# SirenaNextionNRF52.net
KiCad netlist of a schematic drawn in EAGLE
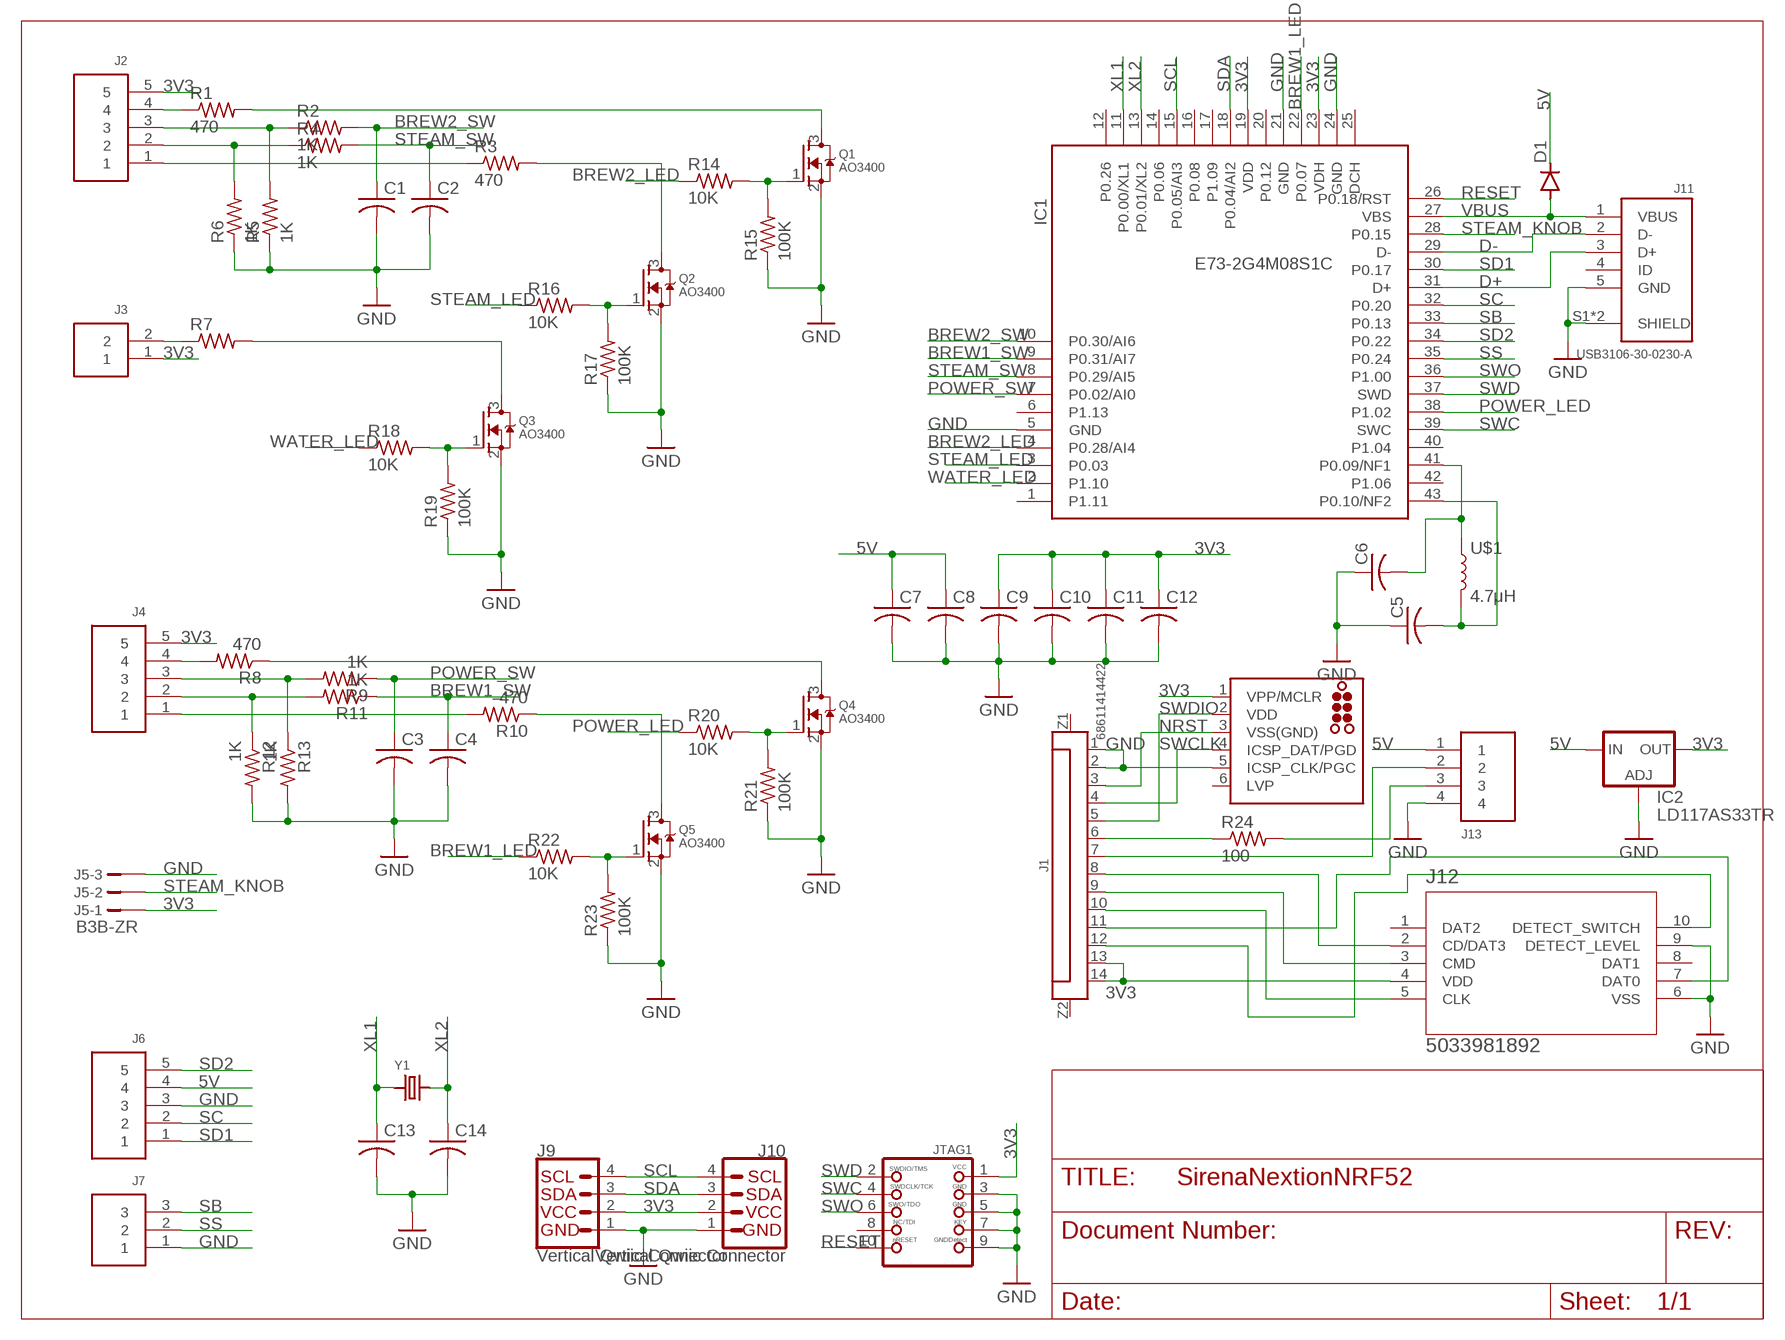
[diagram p0: schematic, sheet 1]

(export (version "E")
  (design (tool "Eeschema 10.0.6"))
  (components
    (comp (ref "C1")
      (value "C-USC0603")
      (footprint "eagle-import:C0603")
      (libsource (lib "eagle-import") (part "C-USC0603"))
    )
    (comp (ref "C2")
      (value "C-USC0603")
      (footprint "eagle-import:C0603")
      (libsource (lib "eagle-import") (part "C-USC0603"))
    )
    (comp (ref "C3")
      (value "C-USC0603")
      (footprint "eagle-import:C0603")
      (libsource (lib "eagle-import") (part "C-USC0603"))
    )
    (comp (ref "C4")
      (value "C-USC0603")
      (footprint "eagle-import:C0603")
      (libsource (lib "eagle-import") (part "C-USC0603"))
    )
    (comp (ref "C5")
      (value "C-USC0603")
      (footprint "eagle-import:C0603")
      (libsource (lib "eagle-import") (part "C-USC0603"))
    )
    (comp (ref "C6")
      (value "C-USC0603")
      (footprint "eagle-import:C0603")
      (libsource (lib "eagle-import") (part "C-USC0603"))
    )
    (comp (ref "C7")
      (value "C-USC0603")
      (footprint "eagle-import:C0603")
      (libsource (lib "eagle-import") (part "C-USC0603"))
    )
    (comp (ref "C8")
      (value "C-USC0603")
      (footprint "eagle-import:C0603")
      (libsource (lib "eagle-import") (part "C-USC0603"))
    )
    (comp (ref "C9")
      (value "C-USC0603")
      (footprint "eagle-import:C0603")
      (libsource (lib "eagle-import") (part "C-USC0603"))
    )
    (comp (ref "C10")
      (value "C-USC0603")
      (footprint "eagle-import:C0603")
      (libsource (lib "eagle-import") (part "C-USC0603"))
    )
    (comp (ref "C11")
      (value "C-USC0603")
      (footprint "eagle-import:C0603")
      (libsource (lib "eagle-import") (part "C-USC0603"))
    )
    (comp (ref "C12")
      (value "C-USC0603")
      (footprint "eagle-import:C0603")
      (libsource (lib "eagle-import") (part "C-USC0603"))
    )
    (comp (ref "C13")
      (value "C-USC0603")
      (footprint "eagle-import:C0603")
      (libsource (lib "eagle-import") (part "C-USC0603"))
    )
    (comp (ref "C14")
      (value "C-USC0603")
      (footprint "eagle-import:C0603")
      (libsource (lib "eagle-import") (part "C-USC0603"))
    )
    (comp (ref "D1")
      (value "DIODE-SOD323-R")
      (footprint "eagle-import:SOD323-R")
      (libsource (lib "eagle-import") (part "DIODE-SOD323-R"))
    )
    (comp (ref "IC1")
      (value "E73-2G4M08S1C")
      (footprint "eagle-import:SMD")
      (libsource (lib "eagle-import") (part "E73-2G4M08S1C"))
    )
    (comp (ref "IC2")
      (value "LD117AS33TR")
      (footprint "eagle-import:SOT223")
      (libsource (lib "eagle-import") (part "LD117A?S33TR"))
    )
    (comp (ref "J1")
      (value "68611414422")
      (footprint "eagle-import:68611414422")
      (libsource (lib "eagle-import") (part "6861XX14422_68611414422"))
    )
    (comp (ref "J2")
      (value "5PINB5B-PH-SM4-TB")
      (footprint "eagle-import:B5B-PH-SM4-TB")
      (libsource (lib "eagle-import") (part "5PINB5B-PH-SM4-TB"))
    )
    (comp (ref "J3")
      (value "2PINB2B-PH-SM4-TB")
      (footprint "eagle-import:B2B-PH-SM4-TB")
      (libsource (lib "eagle-import") (part "2PINB2B-PH-SM4-TB"))
    )
    (comp (ref "J4")
      (value "5PINB5B-PH-SM4-TB")
      (footprint "eagle-import:B5B-PH-SM4-TB")
      (libsource (lib "eagle-import") (part "5PINB5B-PH-SM4-TB"))
    )
    (comp (ref "J5")
      (value "B3B-ZR")
      (footprint "eagle-import:B3B-ZR")
      (libsource (lib "eagle-import") (part "?3B-ZRB"))
    )
    (comp (ref "J6")
      (value "5PINB5B-PH-SM4-TB")
      (footprint "eagle-import:B5B-PH-SM4-TB")
      (libsource (lib "eagle-import") (part "5PINB5B-PH-SM4-TB"))
    )
    (comp (ref "J7")
      (value "3PINB3B-PH-SM4-TB")
      (footprint "eagle-import:B3B-PH-SM4-TB")
      (libsource (lib "eagle-import") (part "3PINB3B-PH-SM4-TB"))
    )
    (comp (ref "J9")
      (value "Vertical Qwiic Connector")
      (footprint "eagle-import:JST04_1MM_VERT")
      (libsource (lib "eagle-import") (part "QWIIC_CONNECTOR"))
    )
    (comp (ref "J10")
      (value "Vertical Qwiic Connector")
      (footprint "eagle-import:JST04_1MM_VERT")
      (libsource (lib "eagle-import") (part "QWIIC_CONNECTOR"))
    )
    (comp (ref "J11")
      (value "USB3106-30-0230-A")
      (footprint "eagle-import:USB3106-30-0230-A")
      (fields
        (field (name "DIGIKEY_PARTNO") "2073-USB3106-30-0230-ATR-ND")
        (field (name "MANUFACTURER") "GCT")
        (field (name "CREATED_BY") "PCBLayout.com")
      )
      (libsource (lib "eagle-import") (part "USB3106-30-0230-A"))
    )
    (comp (ref "J12")
      (value "5033981892")
      (footprint "eagle-import:503398-1892_MOL")
      (fields (field (name "COPYRIGHT") "Copyright (C) 2022 Ultra Librarian. All rights reserved."))
      (libsource (lib "eagle-import") (part "5033981892"))
    )
    (comp (ref "J13")
      (value "4PIN")
      (footprint "eagle-import:B4B-XH-K-S")
      (libsource (lib "eagle-import") (part "4PIN"))
    )
    (comp (ref "J14")
      (value "TC2030-MCP-NL")
      (footprint "eagle-import:TC2030-MCP-NL")
      (libsource (lib "eagle-import") (part "TC2030-MCP-NL"))
    )
    (comp (ref "JTAG1")
      (value "JTAG-CORTEXM3")
      (footprint "eagle-import:2X05_1.27MM_SMT")
      (libsource (lib "eagle-import") (part "JTAG-CORTEXM3"))
    )
    (comp (ref "Q1")
      (value "AO3400")
      (footprint "eagle-import:SOT23")
      (libsource (lib "eagle-import") (part "MOSFET-NREFLOW"))
    )
    (comp (ref "Q2")
      (value "AO3400")
      (footprint "eagle-import:SOT23")
      (libsource (lib "eagle-import") (part "MOSFET-NREFLOW"))
    )
    (comp (ref "Q3")
      (value "AO3400")
      (footprint "eagle-import:SOT23")
      (libsource (lib "eagle-import") (part "MOSFET-NREFLOW"))
    )
    (comp (ref "Q4")
      (value "AO3400")
      (footprint "eagle-import:SOT23")
      (libsource (lib "eagle-import") (part "MOSFET-NREFLOW"))
    )
    (comp (ref "Q5")
      (value "AO3400")
      (footprint "eagle-import:SOT23")
      (libsource (lib "eagle-import") (part "MOSFET-NREFLOW"))
    )
    (comp (ref "R1")
      (value "470")
      (footprint "eagle-import:R0603")
      (libsource (lib "eagle-import") (part "R-US_R0603"))
    )
    (comp (ref "R2")
      (value "1K")
      (footprint "eagle-import:R0603")
      (libsource (lib "eagle-import") (part "R-US_R0603"))
    )
    (comp (ref "R3")
      (value "470")
      (footprint "eagle-import:R0603")
      (libsource (lib "eagle-import") (part "R-US_R0603"))
    )
    (comp (ref "R4")
      (value "1K")
      (footprint "eagle-import:R0603")
      (libsource (lib "eagle-import") (part "R-US_R0603"))
    )
    (comp (ref "R5")
      (value "1K")
      (footprint "eagle-import:R0603")
      (libsource (lib "eagle-import") (part "R-US_R0603"))
    )
    (comp (ref "R6")
      (value "1K")
      (footprint "eagle-import:R0603")
      (libsource (lib "eagle-import") (part "R-US_R0603"))
    )
    (comp (ref "R7")
      (value "R-US_R0603")
      (footprint "eagle-import:R0603")
      (libsource (lib "eagle-import") (part "R-US_R0603"))
    )
    (comp (ref "R8")
      (value "470")
      (footprint "eagle-import:R0603")
      (libsource (lib "eagle-import") (part "R-US_R0603"))
    )
    (comp (ref "R9")
      (value "1K")
      (footprint "eagle-import:R0603")
      (libsource (lib "eagle-import") (part "R-US_R0603"))
    )
    (comp (ref "R10")
      (value "470")
      (footprint "eagle-import:R0603")
      (libsource (lib "eagle-import") (part "R-US_R0603"))
    )
    (comp (ref "R11")
      (value "1K")
      (footprint "eagle-import:R0603")
      (libsource (lib "eagle-import") (part "R-US_R0603"))
    )
    (comp (ref "R12")
      (value "1K")
      (footprint "eagle-import:R0603")
      (libsource (lib "eagle-import") (part "R-US_R0603"))
    )
    (comp (ref "R13")
      (value "1K")
      (footprint "eagle-import:R0603")
      (libsource (lib "eagle-import") (part "R-US_R0603"))
    )
    (comp (ref "R14")
      (value "10K")
      (footprint "eagle-import:R0603")
      (libsource (lib "eagle-import") (part "R-US_R0603"))
    )
    (comp (ref "R15")
      (value "100K")
      (footprint "eagle-import:R0603")
      (libsource (lib "eagle-import") (part "R-US_R0603"))
    )
    (comp (ref "R16")
      (value "10K")
      (footprint "eagle-import:R0603")
      (libsource (lib "eagle-import") (part "R-US_R0603"))
    )
    (comp (ref "R17")
      (value "100K")
      (footprint "eagle-import:R0603")
      (libsource (lib "eagle-import") (part "R-US_R0603"))
    )
    (comp (ref "R18")
      (value "10K")
      (footprint "eagle-import:R0603")
      (libsource (lib "eagle-import") (part "R-US_R0603"))
    )
    (comp (ref "R19")
      (value "100K")
      (footprint "eagle-import:R0603")
      (libsource (lib "eagle-import") (part "R-US_R0603"))
    )
    (comp (ref "R20")
      (value "10K")
      (footprint "eagle-import:R0603")
      (libsource (lib "eagle-import") (part "R-US_R0603"))
    )
    (comp (ref "R21")
      (value "100K")
      (footprint "eagle-import:R0603")
      (libsource (lib "eagle-import") (part "R-US_R0603"))
    )
    (comp (ref "R22")
      (value "10K")
      (footprint "eagle-import:R0603")
      (libsource (lib "eagle-import") (part "R-US_R0603"))
    )
    (comp (ref "R23")
      (value "100K")
      (footprint "eagle-import:R0603")
      (libsource (lib "eagle-import") (part "R-US_R0603"))
    )
    (comp (ref "R24")
      (value "100")
      (footprint "eagle-import:R0603")
      (libsource (lib "eagle-import") (part "R-US_R0603"))
    )
    (comp (ref "U$1")
      (value "4.7μH")
      (footprint "eagle-import:W3102")
      (libsource (lib "eagle-import") (part "RFID_ANTENNA_W3102"))
    )
    (comp (ref "Y1")
      (value "CRYSTAL8X3.8SMT")
      (footprint "eagle-import:CRYSTAL_8X3.8")
      (libsource (lib "eagle-import") (part "CRYSTAL8X3.8SMT"))
    )
  )
  (nets
    (net (code "1") (name "/3V3") (class "Default")
      (node (ref "C10") (pin "1") (pinfunction "1_1") (pintype "passive"))
      (node (ref "C11") (pin "1") (pinfunction "1_1") (pintype "passive"))
      (node (ref "C12") (pin "1") (pinfunction "1_1") (pintype "passive"))
      (node (ref "C9") (pin "1") (pinfunction "1_1") (pintype "passive"))
      (node (ref "IC1") (pin "19") (pinfunction "VDD_19") (pintype "power_in"))
      (node (ref "IC1") (pin "23") (pinfunction "VDH_23") (pintype "power_in"))
      (node (ref "IC2") (pin "4") (pinfunction "OUT_4") (pintype "passive"))
      (node (ref "J1") (pin "13") (pinfunction "13_13") (pintype "passive"))
      (node (ref "J1") (pin "14") (pinfunction "14_14") (pintype "passive"))
      (node (ref "J10") (pin "2") (pinfunction "2_2") (pintype "power_in"))
      (node (ref "J12") (pin "4") (pinfunction "VDD_4") (pintype "power_in"))
      (node (ref "J14") (pin "1") (pinfunction "VPP/MCLR_1") (pintype "passive"))
      (node (ref "J2") (pin "5") (pinfunction "5_5") (pintype "bidirectional"))
      (node (ref "J3") (pin "1") (pinfunction "1_1") (pintype "bidirectional"))
      (node (ref "J4") (pin "5") (pinfunction "5_5") (pintype "bidirectional"))
      (node (ref "J5") (pin "1") (pinfunction "1_1") (pintype "passive"))
      (node (ref "J9") (pin "2") (pinfunction "2_2") (pintype "power_in"))
      (node (ref "JTAG1") (pin "1") (pinfunction "1_1") (pintype "passive"))
    )
    (net (code "2") (name "/5V") (class "Default")
      (node (ref "C7") (pin "1") (pinfunction "1_1") (pintype "passive"))
      (node (ref "C8") (pin "1") (pinfunction "1_1") (pintype "passive"))
      (node (ref "D1") (pin "C") (pinfunction "C_C") (pintype "passive"))
      (node (ref "IC2") (pin "3") (pinfunction "IN_3") (pintype "input"))
      (node (ref "J13") (pin "1") (pinfunction "1_1") (pintype "bidirectional"))
      (node (ref "J6") (pin "4") (pinfunction "4_4") (pintype "bidirectional"))
    )
    (net (code "3") (name "/BREW1_LED") (class "Default")
      (node (ref "IC1") (pin "22") (pinfunction "P0.07_22") (pintype "bidirectional"))
      (node (ref "R22") (pin "1") (pinfunction "1_1") (pintype "passive"))
    )
    (net (code "4") (name "/BREW1_SW") (class "Default")
      (node (ref "C4") (pin "1") (pinfunction "1_1") (pintype "passive"))
      (node (ref "IC1") (pin "9") (pinfunction "P0.31/AI7_9") (pintype "bidirectional"))
      (node (ref "R11") (pin "1") (pinfunction "1_1") (pintype "passive"))
    )
    (net (code "5") (name "/BREW2_LED") (class "Default")
      (node (ref "IC1") (pin "4") (pinfunction "P0.28/AI4_4") (pintype "bidirectional"))
      (node (ref "R14") (pin "1") (pinfunction "1_1") (pintype "passive"))
    )
    (net (code "6") (name "/BREW2_SW") (class "Default")
      (node (ref "C1") (pin "1") (pinfunction "1_1") (pintype "passive"))
      (node (ref "IC1") (pin "10") (pinfunction "P0.30/AI6_10") (pintype "bidirectional"))
      (node (ref "R2") (pin "2") (pinfunction "2_2") (pintype "passive"))
    )
    (net (code "7") (name "/D+") (class "Default")
      (node (ref "IC1") (pin "31") (pinfunction "D+_31") (pintype "bidirectional"))
      (node (ref "J11") (pin "3") (pinfunction "D+_3") (pintype "passive"))
    )
    (net (code "8") (name "/D-") (class "Default")
      (node (ref "IC1") (pin "29") (pinfunction "D-_29") (pintype "bidirectional"))
      (node (ref "J11") (pin "2") (pinfunction "D-_2") (pintype "passive"))
    )
    (net (code "9") (name "/NRST") (class "Default")
      (node (ref "J1") (pin "3") (pinfunction "3_3") (pintype "passive"))
      (node (ref "J14") (pin "3") (pinfunction "VSS(GND)_3") (pintype "power_in"))
    )
    (net (code "10") (name "/POWER_LED") (class "Default")
      (node (ref "IC1") (pin "38") (pinfunction "P1.02_38") (pintype "bidirectional"))
      (node (ref "R20") (pin "1") (pinfunction "1_1") (pintype "passive"))
    )
    (net (code "11") (name "/POWER_SW") (class "Default")
      (node (ref "C3") (pin "1") (pinfunction "1_1") (pintype "passive"))
      (node (ref "IC1") (pin "7") (pinfunction "P0.02/AI0_7") (pintype "bidirectional"))
      (node (ref "R9") (pin "1") (pinfunction "1_1") (pintype "passive"))
    )
    (net (code "12") (name "/RESET") (class "Default")
      (node (ref "IC1") (pin "26") (pinfunction "P0.18/RST_26") (pintype "bidirectional"))
      (node (ref "JTAG1") (pin "10") (pinfunction "10_10") (pintype "passive"))
    )
    (net (code "13") (name "/SB") (class "Default")
      (node (ref "IC1") (pin "33") (pinfunction "P0.13_33") (pintype "bidirectional"))
      (node (ref "J7") (pin "3") (pinfunction "3_3") (pintype "bidirectional"))
    )
    (net (code "14") (name "/SC") (class "Default")
      (node (ref "IC1") (pin "32") (pinfunction "P0.20_32") (pintype "bidirectional"))
      (node (ref "J6") (pin "2") (pinfunction "2_2") (pintype "bidirectional"))
    )
    (net (code "15") (name "/SCL") (class "Default")
      (node (ref "IC1") (pin "15") (pinfunction "P0.05/AI3_15") (pintype "bidirectional"))
      (node (ref "J10") (pin "4") (pinfunction "4_4") (pintype "passive"))
      (node (ref "J9") (pin "4") (pinfunction "4_4") (pintype "passive"))
    )
    (net (code "16") (name "/SD1") (class "Default")
      (node (ref "IC1") (pin "30") (pinfunction "P0.17_30") (pintype "bidirectional"))
      (node (ref "J6") (pin "1") (pinfunction "1_1") (pintype "bidirectional"))
    )
    (net (code "17") (name "/SD2") (class "Default")
      (node (ref "IC1") (pin "34") (pinfunction "P0.22_34") (pintype "bidirectional"))
      (node (ref "J6") (pin "5") (pinfunction "5_5") (pintype "bidirectional"))
    )
    (net (code "18") (name "/SDA") (class "Default")
      (node (ref "IC1") (pin "18") (pinfunction "P0.04/AI2_18") (pintype "bidirectional"))
      (node (ref "J10") (pin "3") (pinfunction "3_3") (pintype "passive"))
      (node (ref "J9") (pin "3") (pinfunction "3_3") (pintype "passive"))
    )
    (net (code "19") (name "/SS") (class "Default")
      (node (ref "IC1") (pin "35") (pinfunction "P0.24_35") (pintype "bidirectional"))
      (node (ref "J7") (pin "2") (pinfunction "2_2") (pintype "bidirectional"))
    )
    (net (code "20") (name "/STEAM_KNOB") (class "Default")
      (node (ref "IC1") (pin "28") (pinfunction "P0.15_28") (pintype "bidirectional"))
      (node (ref "J5") (pin "2") (pinfunction "1_2") (pintype "passive"))
    )
    (net (code "21") (name "/STEAM_LED") (class "Default")
      (node (ref "IC1") (pin "3") (pinfunction "P0.03_3") (pintype "bidirectional"))
      (node (ref "R16") (pin "1") (pinfunction "1_1") (pintype "passive"))
    )
    (net (code "22") (name "/STEAM_SW") (class "Default")
      (node (ref "C2") (pin "1") (pinfunction "1_1") (pintype "passive"))
      (node (ref "IC1") (pin "8") (pinfunction "P0.29/AI5_8") (pintype "bidirectional"))
      (node (ref "R4") (pin "2") (pinfunction "2_2") (pintype "passive"))
    )
    (net (code "23") (name "/SWC") (class "Default")
      (node (ref "IC1") (pin "39") (pinfunction "SWC_39") (pintype "bidirectional"))
      (node (ref "JTAG1") (pin "4") (pinfunction "4_4") (pintype "passive"))
    )
    (net (code "24") (name "/SWCLK") (class "Default")
      (node (ref "J1") (pin "4") (pinfunction "4_4") (pintype "passive"))
      (node (ref "J14") (pin "4") (pinfunction "ICSP_DAT/PGD_4") (pintype "bidirectional"))
    )
    (net (code "25") (name "/SWD") (class "Default")
      (node (ref "IC1") (pin "37") (pinfunction "SWD_37") (pintype "bidirectional"))
      (node (ref "JTAG1") (pin "2") (pinfunction "2_2") (pintype "passive"))
    )
    (net (code "26") (name "/SWDIO") (class "Default")
      (node (ref "J1") (pin "5") (pinfunction "5_5") (pintype "passive"))
      (node (ref "J14") (pin "2") (pinfunction "VDD_2") (pintype "power_in"))
    )
    (net (code "27") (name "/SWO") (class "Default")
      (node (ref "IC1") (pin "36") (pinfunction "P1.00_36") (pintype "bidirectional"))
      (node (ref "JTAG1") (pin "6") (pinfunction "6_6") (pintype "passive"))
    )
    (net (code "28") (name "/VBUS") (class "Default")
      (node (ref "D1") (pin "A") (pinfunction "A_A") (pintype "passive"))
      (node (ref "IC1") (pin "27") (pinfunction "VBS_27") (pintype "power_in"))
      (node (ref "J11") (pin "1") (pinfunction "VBUS_1") (pintype "passive"))
    )
    (net (code "29") (name "/WATER_LED") (class "Default")
      (node (ref "IC1") (pin "2") (pinfunction "P1.10_2") (pintype "bidirectional"))
      (node (ref "R18") (pin "1") (pinfunction "1_1") (pintype "passive"))
    )
    (net (code "30") (name "/XL1") (class "Default")
      (node (ref "C13") (pin "1") (pinfunction "1_1") (pintype "passive"))
      (node (ref "IC1") (pin "11") (pinfunction "P0.00/XL1_11") (pintype "bidirectional"))
      (node (ref "Y1") (pin "P$1") (pinfunction "1_P$1") (pintype "passive"))
    )
    (net (code "31") (name "/XL2") (class "Default")
      (node (ref "C14") (pin "1") (pinfunction "1_1") (pintype "passive"))
      (node (ref "IC1") (pin "13") (pinfunction "P0.01/XL2_13") (pintype "bidirectional"))
      (node (ref "Y1") (pin "P$4") (pinfunction "2_P$4") (pintype "passive"))
    )
    (net (code "32") (name "GND") (class "Default")
      (node (ref "C1") (pin "2") (pinfunction "2_2") (pintype "passive"))
      (node (ref "C10") (pin "2") (pinfunction "2_2") (pintype "passive"))
      (node (ref "C11") (pin "2") (pinfunction "2_2") (pintype "passive"))
      (node (ref "C12") (pin "2") (pinfunction "2_2") (pintype "passive"))
      (node (ref "C13") (pin "2") (pinfunction "2_2") (pintype "passive"))
      (node (ref "C14") (pin "2") (pinfunction "2_2") (pintype "passive"))
      (node (ref "C2") (pin "2") (pinfunction "2_2") (pintype "passive"))
      (node (ref "C3") (pin "2") (pinfunction "2_2") (pintype "passive"))
      (node (ref "C4") (pin "2") (pinfunction "2_2") (pintype "passive"))
      (node (ref "C5") (pin "1") (pinfunction "1_1") (pintype "passive"))
      (node (ref "C6") (pin "1") (pinfunction "1_1") (pintype "passive"))
      (node (ref "C7") (pin "2") (pinfunction "2_2") (pintype "passive"))
      (node (ref "C8") (pin "2") (pinfunction "2_2") (pintype "passive"))
      (node (ref "C9") (pin "2") (pinfunction "2_2") (pintype "passive"))
      (node (ref "IC1") (pin "21") (pinfunction "GND_21") (pintype "power_in"))
      (node (ref "IC1") (pin "24") (pinfunction "GND_24") (pintype "power_in"))
      (node (ref "IC1") (pin "5") (pinfunction "GND_5") (pintype "power_in"))
      (node (ref "IC2") (pin "1") (pinfunction "ADJ_1") (pintype "input"))
      (node (ref "J1") (pin "1") (pinfunction "1_1") (pintype "passive"))
      (node (ref "J1") (pin "2") (pinfunction "2_2") (pintype "passive"))
      (node (ref "J10") (pin "1") (pinfunction "1_1") (pintype "power_in"))
      (node (ref "J11") (pin "5") (pinfunction "GND_5") (pintype "passive"))
      (node (ref "J11") (pin "S1") (pinfunction "SHIELD_S1") (pintype "power_in"))
      (node (ref "J11") (pin "S2") (pinfunction "SHIELD_S2") (pintype "power_in"))
      (node (ref "J12") (pin "6") (pinfunction "VSS_6") (pintype "passive"))
      (node (ref "J12") (pin "9") (pinfunction "DETECT_LEVEL_9") (pintype "passive"))
      (node (ref "J13") (pin "4") (pinfunction "4_4") (pintype "bidirectional"))
      (node (ref "J14") (pin "5") (pinfunction "ICSP_CLK/PGC_5") (pintype "output"))
      (node (ref "J5") (pin "3") (pinfunction "1_3") (pintype "passive"))
      (node (ref "J6") (pin "3") (pinfunction "3_3") (pintype "bidirectional"))
      (node (ref "J7") (pin "1") (pinfunction "1_1") (pintype "bidirectional"))
      (node (ref "J9") (pin "1") (pinfunction "1_1") (pintype "power_in"))
      (node (ref "JTAG1") (pin "3") (pinfunction "3_3") (pintype "passive"))
      (node (ref "JTAG1") (pin "5") (pinfunction "5_5") (pintype "passive"))
      (node (ref "JTAG1") (pin "7") (pinfunction "7_7") (pintype "passive"))
      (node (ref "JTAG1") (pin "9") (pinfunction "9_9") (pintype "passive"))
      (node (ref "Q1") (pin "2") (pinfunction "S_2") (pintype "bidirectional"))
      (node (ref "Q2") (pin "2") (pinfunction "S_2") (pintype "bidirectional"))
      (node (ref "Q3") (pin "2") (pinfunction "S_2") (pintype "bidirectional"))
      (node (ref "Q4") (pin "2") (pinfunction "S_2") (pintype "bidirectional"))
      (node (ref "Q5") (pin "2") (pinfunction "S_2") (pintype "bidirectional"))
      (node (ref "R12") (pin "2") (pinfunction "2_2") (pintype "passive"))
      (node (ref "R13") (pin "2") (pinfunction "2_2") (pintype "passive"))
      (node (ref "R15") (pin "1") (pinfunction "1_1") (pintype "passive"))
      (node (ref "R17") (pin "1") (pinfunction "1_1") (pintype "passive"))
      (node (ref "R19") (pin "1") (pinfunction "1_1") (pintype "passive"))
      (node (ref "R21") (pin "1") (pinfunction "1_1") (pintype "passive"))
      (node (ref "R23") (pin "1") (pinfunction "1_1") (pintype "passive"))
      (node (ref "R5") (pin "1") (pinfunction "1_1") (pintype "passive"))
      (node (ref "R6") (pin "1") (pinfunction "1_1") (pintype "passive"))
    )
    (net (code "33") (name "Net-(IC1-P0.09{slash}NF1)") (class "Default")
      (node (ref "C6") (pin "2") (pinfunction "2_2") (pintype "passive"))
      (node (ref "IC1") (pin "41") (pinfunction "P0.09/NF1_41") (pintype "bidirectional"))
      (node (ref "U$1") (pin "1") (pinfunction "1_1") (pintype "passive"))
    )
    (net (code "34") (name "Net-(IC1-P0.10{slash}NF2)") (class "Default")
      (node (ref "C5") (pin "2") (pinfunction "2_2") (pintype "passive"))
      (node (ref "IC1") (pin "43") (pinfunction "P0.10/NF2_43") (pintype "bidirectional"))
      (node (ref "U$1") (pin "2") (pinfunction "2_2") (pintype "passive"))
    )
    (net (code "35") (name "Net-(J1-Pad6)") (class "Default")
      (node (ref "J1") (pin "6") (pinfunction "6_6") (pintype "passive"))
      (node (ref "R24") (pin "1") (pinfunction "1_1") (pintype "passive"))
    )
    (net (code "36") (name "Net-(J1-Pad7)") (class "Default")
      (node (ref "J1") (pin "7") (pinfunction "7_7") (pintype "passive"))
      (node (ref "J13") (pin "2") (pinfunction "2_2") (pintype "bidirectional"))
    )
    (net (code "37") (name "Net-(J2-Pad1)") (class "Default")
      (node (ref "J2") (pin "1") (pinfunction "1_1") (pintype "bidirectional"))
      (node (ref "R3") (pin "1") (pinfunction "1_1") (pintype "passive"))
    )
    (net (code "38") (name "Net-(J2-Pad2)") (class "Default")
      (node (ref "J2") (pin "2") (pinfunction "2_2") (pintype "bidirectional"))
      (node (ref "R4") (pin "1") (pinfunction "1_1") (pintype "passive"))
      (node (ref "R6") (pin "2") (pinfunction "2_2") (pintype "passive"))
    )
    (net (code "39") (name "Net-(J2-Pad3)") (class "Default")
      (node (ref "J2") (pin "3") (pinfunction "3_3") (pintype "bidirectional"))
      (node (ref "R2") (pin "1") (pinfunction "1_1") (pintype "passive"))
      (node (ref "R5") (pin "2") (pinfunction "2_2") (pintype "passive"))
    )
    (net (code "40") (name "Net-(J2-Pad4)") (class "Default")
      (node (ref "J2") (pin "4") (pinfunction "4_4") (pintype "bidirectional"))
      (node (ref "R1") (pin "1") (pinfunction "1_1") (pintype "passive"))
    )
    (net (code "41") (name "Net-(J3-Pad2)") (class "Default")
      (node (ref "J3") (pin "2") (pinfunction "2_2") (pintype "bidirectional"))
      (node (ref "R7") (pin "1") (pinfunction "1_1") (pintype "passive"))
    )
    (net (code "42") (name "Net-(J4-Pad1)") (class "Default")
      (node (ref "J4") (pin "1") (pinfunction "1_1") (pintype "bidirectional"))
      (node (ref "R10") (pin "2") (pinfunction "2_2") (pintype "passive"))
    )
    (net (code "43") (name "Net-(J4-Pad2)") (class "Default")
      (node (ref "J4") (pin "2") (pinfunction "2_2") (pintype "bidirectional"))
      (node (ref "R11") (pin "2") (pinfunction "2_2") (pintype "passive"))
      (node (ref "R12") (pin "1") (pinfunction "1_1") (pintype "passive"))
    )
    (net (code "44") (name "Net-(J4-Pad3)") (class "Default")
      (node (ref "J4") (pin "3") (pinfunction "3_3") (pintype "bidirectional"))
      (node (ref "R13") (pin "1") (pinfunction "1_1") (pintype "passive"))
      (node (ref "R9") (pin "2") (pinfunction "2_2") (pintype "passive"))
    )
    (net (code "45") (name "Net-(J4-Pad4)") (class "Default")
      (node (ref "J4") (pin "4") (pinfunction "4_4") (pintype "bidirectional"))
      (node (ref "R8") (pin "2") (pinfunction "2_2") (pintype "passive"))
    )
    (net (code "46") (name "Net-(J12-CD{slash}DAT3)") (class "Default")
      (node (ref "J1") (pin "8") (pinfunction "8_8") (pintype "passive"))
      (node (ref "J12") (pin "2") (pinfunction "CD/DAT3_2") (pintype "passive"))
    )
    (net (code "47") (name "Net-(J12-CLK)") (class "Default")
      (node (ref "J1") (pin "10") (pinfunction "10_10") (pintype "passive"))
      (node (ref "J12") (pin "5") (pinfunction "CLK_5") (pintype "passive"))
    )
    (net (code "48") (name "Net-(J12-CMD)") (class "Default")
      (node (ref "J1") (pin "9") (pinfunction "9_9") (pintype "passive"))
      (node (ref "J12") (pin "3") (pinfunction "CMD_3") (pintype "passive"))
    )
    (net (code "49") (name "Net-(J12-DAT0)") (class "Default")
      (node (ref "J1") (pin "11") (pinfunction "11_11") (pintype "passive"))
      (node (ref "J12") (pin "7") (pinfunction "DAT0_7") (pintype "bidirectional"))
    )
    (net (code "50") (name "Net-(J12-DETECT_SWITCH)") (class "Default")
      (node (ref "J1") (pin "12") (pinfunction "12_12") (pintype "passive"))
      (node (ref "J12") (pin "10") (pinfunction "DETECT_SWITCH_10") (pintype "passive"))
    )
    (net (code "51") (name "Net-(J13-Pad3)") (class "Default")
      (node (ref "J13") (pin "3") (pinfunction "3_3") (pintype "bidirectional"))
      (node (ref "R24") (pin "2") (pinfunction "2_2") (pintype "passive"))
    )
    (net (code "52") (name "Net-(Q1-D)") (class "Default")
      (node (ref "Q1") (pin "3") (pinfunction "D_3") (pintype "bidirectional"))
      (node (ref "R1") (pin "2") (pinfunction "2_2") (pintype "passive"))
    )
    (net (code "53") (name "Net-(Q1-G)") (class "Default")
      (node (ref "Q1") (pin "1") (pinfunction "G_1") (pintype "bidirectional"))
      (node (ref "R14") (pin "2") (pinfunction "2_2") (pintype "passive"))
      (node (ref "R15") (pin "2") (pinfunction "2_2") (pintype "passive"))
    )
    (net (code "54") (name "Net-(Q2-D)") (class "Default")
      (node (ref "Q2") (pin "3") (pinfunction "D_3") (pintype "bidirectional"))
      (node (ref "R3") (pin "2") (pinfunction "2_2") (pintype "passive"))
    )
    (net (code "55") (name "Net-(Q2-G)") (class "Default")
      (node (ref "Q2") (pin "1") (pinfunction "G_1") (pintype "bidirectional"))
      (node (ref "R16") (pin "2") (pinfunction "2_2") (pintype "passive"))
      (node (ref "R17") (pin "2") (pinfunction "2_2") (pintype "passive"))
    )
    (net (code "56") (name "Net-(Q3-D)") (class "Default")
      (node (ref "Q3") (pin "3") (pinfunction "D_3") (pintype "bidirectional"))
      (node (ref "R7") (pin "2") (pinfunction "2_2") (pintype "passive"))
    )
    (net (code "57") (name "Net-(Q3-G)") (class "Default")
      (node (ref "Q3") (pin "1") (pinfunction "G_1") (pintype "bidirectional"))
      (node (ref "R18") (pin "2") (pinfunction "2_2") (pintype "passive"))
      (node (ref "R19") (pin "2") (pinfunction "2_2") (pintype "passive"))
    )
    (net (code "58") (name "Net-(Q4-D)") (class "Default")
      (node (ref "Q4") (pin "3") (pinfunction "D_3") (pintype "bidirectional"))
      (node (ref "R8") (pin "1") (pinfunction "1_1") (pintype "passive"))
    )
    (net (code "59") (name "Net-(Q4-G)") (class "Default")
      (node (ref "Q4") (pin "1") (pinfunction "G_1") (pintype "bidirectional"))
      (node (ref "R20") (pin "2") (pinfunction "2_2") (pintype "passive"))
      (node (ref "R21") (pin "2") (pinfunction "2_2") (pintype "passive"))
    )
    (net (code "60") (name "Net-(Q5-D)") (class "Default")
      (node (ref "Q5") (pin "3") (pinfunction "D_3") (pintype "bidirectional"))
      (node (ref "R10") (pin "1") (pinfunction "1_1") (pintype "passive"))
    )
    (net (code "61") (name "Net-(Q5-G)") (class "Default")
      (node (ref "Q5") (pin "1") (pinfunction "G_1") (pintype "bidirectional"))
      (node (ref "R22") (pin "2") (pinfunction "2_2") (pintype "passive"))
      (node (ref "R23") (pin "2") (pinfunction "2_2") (pintype "passive"))
    )
    (net (code "62") (name "unconnected-(IC1-DCH-Pad25)") (class "Default")
      (node (ref "IC1") (pin "25") (pinfunction "DCH_25") (pintype "bidirectional"))
    )
    (net (code "63") (name "unconnected-(IC1-P0.06-Pad14)") (class "Default")
      (node (ref "IC1") (pin "14") (pinfunction "P0.06_14") (pintype "bidirectional"))
    )
    (net (code "64") (name "unconnected-(IC1-P0.08-Pad16)") (class "Default")
      (node (ref "IC1") (pin "16") (pinfunction "P0.08_16") (pintype "bidirectional"))
    )
    (net (code "65") (name "unconnected-(IC1-P0.12-Pad20)") (class "Default")
      (node (ref "IC1") (pin "20") (pinfunction "P0.12_20") (pintype "bidirectional"))
    )
    (net (code "66") (name "unconnected-(IC1-P0.26-Pad12)") (class "Default")
      (node (ref "IC1") (pin "12") (pinfunction "P0.26_12") (pintype "bidirectional"))
    )
    (net (code "67") (name "unconnected-(IC1-P1.04-Pad40)") (class "Default")
      (node (ref "IC1") (pin "40") (pinfunction "P1.04_40") (pintype "bidirectional"))
    )
    (net (code "68") (name "unconnected-(IC1-P1.06-Pad42)") (class "Default")
      (node (ref "IC1") (pin "42") (pinfunction "P1.06_42") (pintype "bidirectional"))
    )
    (net (code "69") (name "unconnected-(IC1-P1.09-Pad17)") (class "Default")
      (node (ref "IC1") (pin "17") (pinfunction "P1.09_17") (pintype "bidirectional"))
    )
    (net (code "70") (name "unconnected-(IC1-P1.11-Pad1)") (class "Default")
      (node (ref "IC1") (pin "1") (pinfunction "P1.11_1") (pintype "bidirectional"))
    )
    (net (code "71") (name "unconnected-(IC1-P1.13-Pad6)") (class "Default")
      (node (ref "IC1") (pin "6") (pinfunction "P1.13_6") (pintype "bidirectional"))
    )
    (net (code "72") (name "unconnected-(J1-PadZ1)") (class "Default")
      (node (ref "J1") (pin "Z1") (pinfunction "Z1_Z1") (pintype "passive"))
    )
    (net (code "73") (name "unconnected-(J1-PadZ2)") (class "Default")
      (node (ref "J1") (pin "Z2") (pinfunction "Z2_Z2") (pintype "passive"))
    )
    (net (code "74") (name "unconnected-(J11-ID-Pad4)") (class "Default")
      (node (ref "J11") (pin "4") (pinfunction "ID_4") (pintype "passive"))
    )
    (net (code "75") (name "unconnected-(J12-DAT1-Pad8)") (class "Default")
      (node (ref "J12") (pin "8") (pinfunction "DAT1_8") (pintype "bidirectional"))
    )
    (net (code "76") (name "unconnected-(J12-DAT2-Pad1)") (class "Default")
      (node (ref "J12") (pin "1") (pinfunction "DAT2_1") (pintype "bidirectional"))
    )
    (net (code "77") (name "unconnected-(J14-LVP-Pad6)") (class "Default")
      (node (ref "J14") (pin "6") (pinfunction "LVP_6") (pintype "bidirectional"))
    )
    (net (code "78") (name "unconnected-(JTAG1-Pad8)") (class "Default")
      (node (ref "JTAG1") (pin "8") (pinfunction "8_8") (pintype "passive"))
    )
  )
)
